# FORKGUARD_MAIN_BOARD.net
KiCad netlist of a schematic drawn in EasyEDA Pro
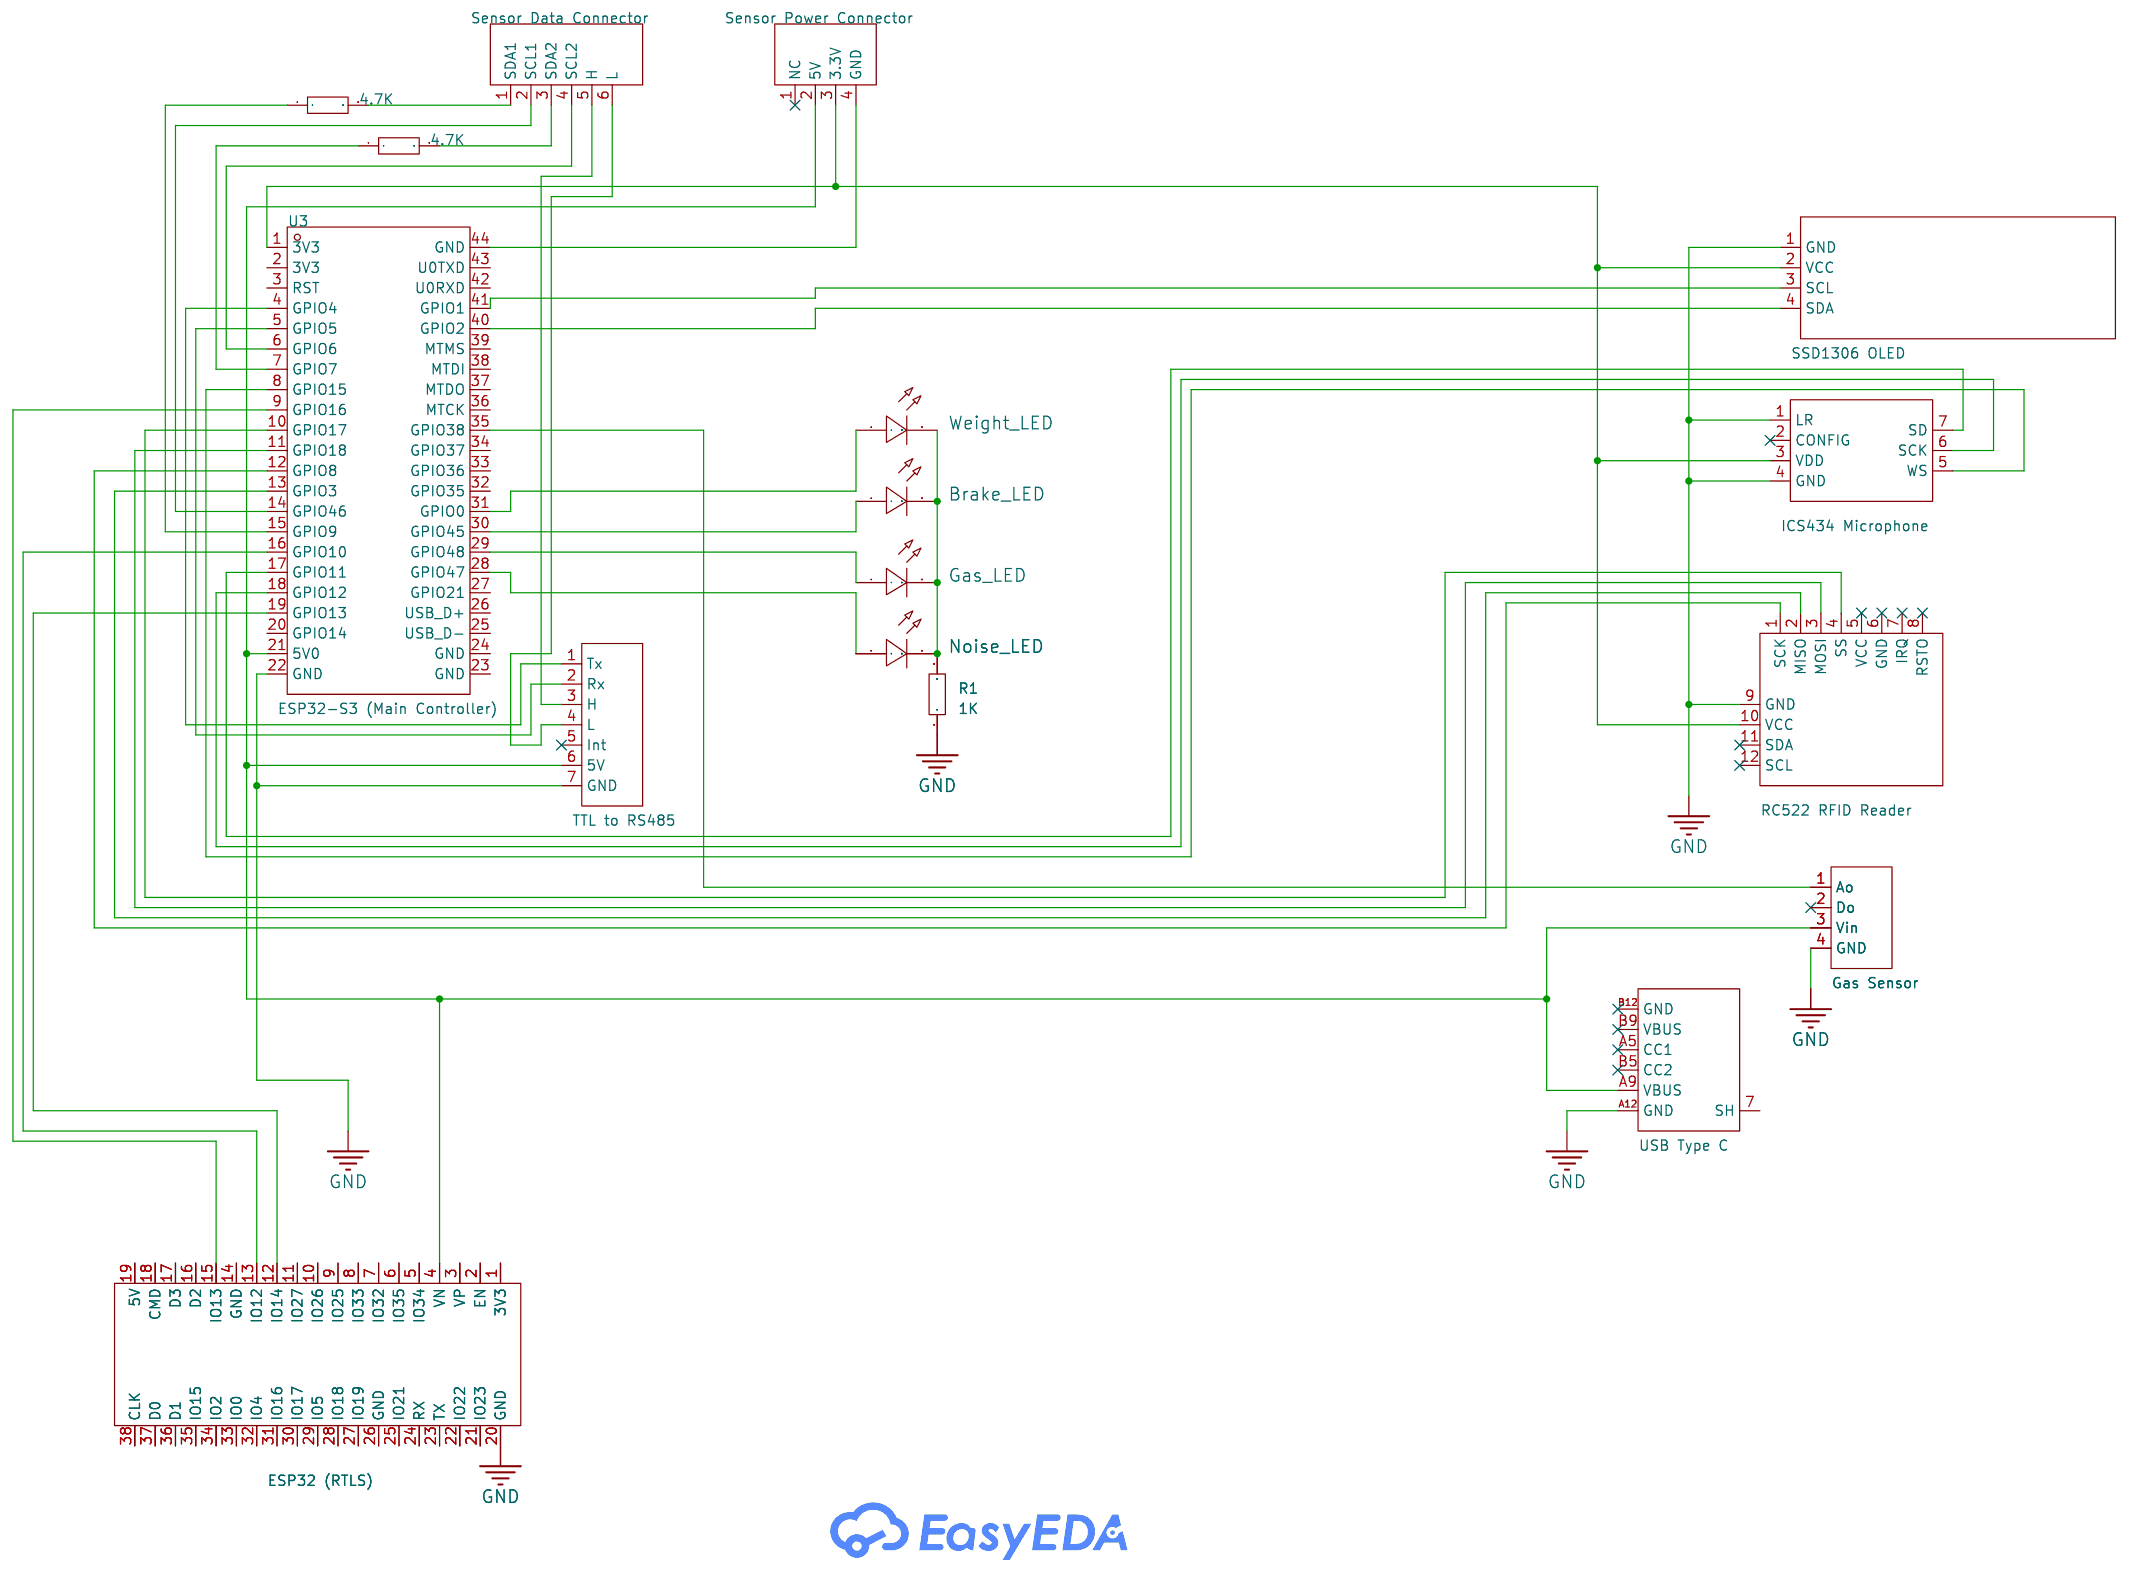
[diagram p0: schematic sheet]

(export (version "E")
  (design (tool "Eeschema 10.0.6"))
  (components
    (comp (ref "Brake_LED")
      (value "~")
      (footprint "easyedapro:LED0402-RD_YELLOW")
      (libsource (lib "easyedapro") (part "LED_R"))
    )
    (comp (ref "Display")
      (value "SSD1306 OLED")
      (footprint "easyedapro:OLED-TH_4P-L27.8-W27.3_MC096GW")
      (fields (field (name "Manufacturer Part") "MC096GW"))
      (libsource (lib "easyedapro") (part "MC096GW"))
    )
    (comp (ref "Gas_LED")
      (value "~")
      (footprint "easyedapro:LED0402-RD_YELLOW")
      (libsource (lib "easyedapro") (part "LED_R"))
    )
    (comp (ref "H1")
      (value "Sensor Data Connector")
      (footprint "easyedapro:HDR-TH_TW-06-01-T-S-150-085")
      (fields
        (field (name "Manufacturer Part") "TW-06-08-L-S-580-150")
        (field (name "Manufacturer") "SAMTEC")
      )
      (libsource (lib "easyedapro") (part "TW-06-08-L-S-580-150"))
    )
    (comp (ref "H2")
      (value "Sensor Power Connector")
      (footprint "easyedapro:HDR-TH_TW-04-06-T-S-433-120")
      (fields
        (field (name "Manufacturer Part") "TW-04-05-L-S-275-158")
        (field (name "Manufacturer") "SAMTEC")
      )
      (libsource (lib "easyedapro") (part "TW-04-05-L-S-275-158"))
    )
    (comp (ref "H5")
      (value "TTL to RS485")
      (footprint "easyedapro:HDR-TH_7P-P2.54_PBC07SAEN")
      (fields (field (name "Manufacturer Part") "PEC07SADN") (field (name "Manufacturer") "Sullins"))
      (libsource (lib "easyedapro") (part "PEC07SADN"))
    )
    (comp (ref "H6")
      (value "Gas Sensor")
      (footprint "easyedapro:HDR-TH_4P-P2.54-V-M_2")
      (fields (field (name "Manufacturer Part") "PEC04SFDN") (field (name "Manufacturer") "Sullins"))
      (libsource (lib "easyedapro") (part "PEC04SFDN"))
    )
    (comp (ref "Noise_LED")
      (value "~")
      (footprint "easyedapro:LED0402-RD_YELLOW")
      (libsource (lib "easyedapro") (part "LED_R"))
    )
    (comp (ref "R1") (value "10K") (footprint "easyedapro:R0603") (libsource (lib "easyedapro") (part "Res")))
    (comp (ref "R2") (value "10K") (footprint "easyedapro:R0603") (libsource (lib "easyedapro") (part "Res")))
    (comp (ref "R3")
      (value "10kΩ")
      (footprint "easyedapro:R0603")
      (libsource (lib "easyedapro") (part "Res"))
    )
    (comp (ref "U3")
      (value "ESP32-S3 (Main Controller)")
      (footprint "easyedapro:COMM-TH_L63.3-W25.4-P2.54-LS22.86")
      (fields (field (name "Manufacturer Part") "ESP32-S3-DEV-KIT-N8R8"))
      (libsource (lib "easyedapro") (part "ESP32-S3-DEV-KIT-N8R8"))
    )
    (comp (ref "U5")
      (value "ICS434 Microphone")
      (footprint "easyedapro:MIC-SMD_7P-L4.0-W3.0-P2.15-TL")
      (fields (field (name "Manufacturer Part") "DMM-4026-B-I2S-R") (field (name "Manufacturer") "PUIAUDIO"))
      (libsource (lib "easyedapro") (part "DMM-4026-B-I2S-R_C3171792"))
    )
    (comp (ref "U6")
      (value "RC522 RFID Reader")
      (footprint "easyedapro:COMM-TH_L42.7-W40.4_PN532_NFC_RFID")
      (fields (field (name "Manufacturer Part") "PN532 NFC RFID Module v4"))
      (libsource (lib "easyedapro") (part "PN532 NFC RFID MODULE V4"))
    )
    (comp (ref "U7")
      (value "ESP32 (RTLS)")
      (footprint "easyedapro:BULETM-SMD_ESP32-DEVKITC")
      (fields
        (field (name "Manufacturer Part") "ESP32-DEVKITC-VE")
        (field (name "Manufacturer") "ESPRESSIF(乐鑫)")
      )
      (libsource (lib "easyedapro") (part "ESP32-DEVKITC-VE"))
    )
    (comp (ref "USB1")
      (value "USB Type C")
      (footprint "easyedapro:USB-SMD_TYPE-C6P-ST")
      (fields (field (name "Manufacturer Part") "TCR51-65120601"))
      (libsource (lib "easyedapro") (part "TCR51-65120601"))
    )
    (comp (ref "Weight_LED")
      (value "~")
      (footprint "easyedapro:LED0402-RD_YELLOW")
      (libsource (lib "easyedapro") (part "LED_R"))
    )
  )
  (nets
    (net (code "1") (name "GND") (class "Default")
      (node (ref "Display") (pin "1") (pinfunction "GND_1") (pintype "unspecified"))
      (node (ref "H5") (pin "7") (pinfunction "GND_7") (pintype "unspecified"))
      (node (ref "H6") (pin "4") (pinfunction "GND_4") (pintype "unspecified"))
      (node (ref "R1") (pin "1") (pinfunction "1_1") (pintype "input"))
      (node (ref "U3") (pin "22") (pinfunction "GND_22") (pintype "unspecified"))
      (node (ref "U5") (pin "1") (pinfunction "LR_1") (pintype "unspecified"))
      (node (ref "U5") (pin "4") (pinfunction "GND_4") (pintype "unspecified"))
      (node (ref "U6") (pin "9") (pinfunction "GND_9") (pintype "unspecified"))
      (node (ref "U7") (pin "20") (pinfunction "GND_20") (pintype "unspecified"))
      (node (ref "USB1") (pin "A12") (pinfunction "GND_A12") (pintype "unspecified"))
    )
    (net (code "2") (name "Net-(Brake_LED-A)") (class "Default")
      (node (ref "Brake_LED") (pin "1") (pinfunction "A_1") (pintype "input"))
      (node (ref "U3") (pin "30") (pinfunction "GPIO45_30") (pintype "unspecified"))
    )
    (net (code "3") (name "Net-(Brake_LED-C)") (class "Default")
      (node (ref "Brake_LED") (pin "2") (pinfunction "C_2") (pintype "input"))
      (node (ref "Gas_LED") (pin "2") (pinfunction "C_2") (pintype "input"))
      (node (ref "Noise_LED") (pin "2") (pinfunction "C_2") (pintype "input"))
      (node (ref "R1") (pin "2") (pinfunction "2_2") (pintype "input"))
      (node (ref "Weight_LED") (pin "2") (pinfunction "C_2") (pintype "input"))
    )
    (net (code "4") (name "Net-(Display-SCL)") (class "Default")
      (node (ref "Display") (pin "3") (pinfunction "SCL_3") (pintype "unspecified"))
      (node (ref "U3") (pin "41") (pinfunction "GPIO1_41") (pintype "unspecified"))
    )
    (net (code "5") (name "Net-(Display-SDA)") (class "Default")
      (node (ref "Display") (pin "4") (pinfunction "SDA_4") (pintype "unspecified"))
      (node (ref "U3") (pin "40") (pinfunction "GPIO2_40") (pintype "unspecified"))
    )
    (net (code "6") (name "Net-(Display-VCC)") (class "Default")
      (node (ref "Display") (pin "2") (pinfunction "VCC_2") (pintype "unspecified"))
      (node (ref "H2") (pin "3") (pinfunction "3.3V_3") (pintype "unspecified"))
      (node (ref "U3") (pin "1") (pinfunction "3V3_1") (pintype "unspecified"))
      (node (ref "U5") (pin "3") (pinfunction "VDD_3") (pintype "unspecified"))
      (node (ref "U6") (pin "10") (pinfunction "VCC_10") (pintype "unspecified"))
    )
    (net (code "7") (name "Net-(Gas_LED-A)") (class "Default")
      (node (ref "Gas_LED") (pin "1") (pinfunction "A_1") (pintype "input"))
      (node (ref "U3") (pin "29") (pinfunction "GPIO48_29") (pintype "unspecified"))
    )
    (net (code "8") (name "Net-(H1-H)") (class "Default")
      (node (ref "H1") (pin "5") (pinfunction "H_5") (pintype "unspecified"))
      (node (ref "H5") (pin "3") (pinfunction "H_3") (pintype "unspecified"))
    )
    (net (code "9") (name "Net-(H1-L)") (class "Default")
      (node (ref "H1") (pin "6") (pinfunction "L_6") (pintype "unspecified"))
      (node (ref "H5") (pin "4") (pinfunction "L_4") (pintype "unspecified"))
    )
    (net (code "10") (name "Net-(H1-SCL1)") (class "Default")
      (node (ref "H1") (pin "2") (pinfunction "SCL1_2") (pintype "unspecified"))
      (node (ref "U3") (pin "14") (pinfunction "GPIO46_14") (pintype "unspecified"))
    )
    (net (code "11") (name "Net-(H1-SCL2)") (class "Default")
      (node (ref "H1") (pin "4") (pinfunction "SCL2_4") (pintype "unspecified"))
      (node (ref "U3") (pin "6") (pinfunction "GPIO6_6") (pintype "unspecified"))
    )
    (net (code "12") (name "Net-(H1-SDA1)") (class "Default")
      (node (ref "H1") (pin "1") (pinfunction "SDA1_1") (pintype "unspecified"))
      (node (ref "R2") (pin "2") (pinfunction "2_2") (pintype "input"))
    )
    (net (code "13") (name "Net-(H1-SDA2)") (class "Default")
      (node (ref "H1") (pin "3") (pinfunction "SDA2_3") (pintype "unspecified"))
      (node (ref "R3") (pin "2") (pinfunction "2_2") (pintype "input"))
    )
    (net (code "14") (name "Net-(H2-5V)") (class "Default")
      (node (ref "H2") (pin "2") (pinfunction "5V_2") (pintype "unspecified"))
      (node (ref "H5") (pin "6") (pinfunction "5V_6") (pintype "unspecified"))
      (node (ref "H6") (pin "3") (pinfunction "Vin_3") (pintype "unspecified"))
      (node (ref "U3") (pin "21") (pinfunction "5V0_21") (pintype "unspecified"))
      (node (ref "U7") (pin "4") (pinfunction "VN_4") (pintype "unspecified"))
      (node (ref "USB1") (pin "A9") (pinfunction "VBUS_A9") (pintype "unspecified"))
    )
    (net (code "15") (name "Net-(H2-GND)") (class "Default")
      (node (ref "H2") (pin "4") (pinfunction "GND_4") (pintype "unspecified"))
      (node (ref "U3") (pin "44") (pinfunction "GND_44") (pintype "unspecified"))
    )
    (net (code "16") (name "Net-(H5-Rx)") (class "Default")
      (node (ref "H5") (pin "2") (pinfunction "Rx_2") (pintype "unspecified"))
      (node (ref "U3") (pin "5") (pinfunction "GPIO5_5") (pintype "unspecified"))
    )
    (net (code "17") (name "Net-(H5-Tx)") (class "Default")
      (node (ref "H5") (pin "1") (pinfunction "Tx_1") (pintype "unspecified"))
      (node (ref "U3") (pin "4") (pinfunction "GPIO4_4") (pintype "unspecified"))
    )
    (net (code "18") (name "Net-(H6-Ao)") (class "Default")
      (node (ref "H6") (pin "1") (pinfunction "Ao_1") (pintype "unspecified"))
      (node (ref "U3") (pin "35") (pinfunction "GPIO38_35") (pintype "unspecified"))
    )
    (net (code "19") (name "Net-(Noise_LED-A)") (class "Default")
      (node (ref "Noise_LED") (pin "1") (pinfunction "A_1") (pintype "input"))
      (node (ref "U3") (pin "28") (pinfunction "GPIO47_28") (pintype "unspecified"))
    )
    (net (code "20") (name "Net-(U3-GPIO0)") (class "Default")
      (node (ref "U3") (pin "31") (pinfunction "GPIO0_31") (pintype "unspecified"))
      (node (ref "Weight_LED") (pin "1") (pinfunction "A_1") (pintype "input"))
    )
    (net (code "21") (name "Net-(U3-GPIO3)") (class "Default")
      (node (ref "U3") (pin "13") (pinfunction "GPIO3_13") (pintype "unspecified"))
      (node (ref "U6") (pin "2") (pinfunction "MISO_2") (pintype "unspecified"))
    )
    (net (code "22") (name "Net-(U3-GPIO7)") (class "Default")
      (node (ref "R3") (pin "1") (pinfunction "1_1") (pintype "input"))
      (node (ref "U3") (pin "7") (pinfunction "GPIO7_7") (pintype "unspecified"))
    )
    (net (code "23") (name "Net-(U3-GPIO8)") (class "Default")
      (node (ref "U3") (pin "12") (pinfunction "GPIO8_12") (pintype "unspecified"))
      (node (ref "U6") (pin "1") (pinfunction "SCK_1") (pintype "unspecified"))
    )
    (net (code "24") (name "Net-(U3-GPIO9)") (class "Default")
      (node (ref "R2") (pin "1") (pinfunction "1_1") (pintype "input"))
      (node (ref "U3") (pin "15") (pinfunction "GPIO9_15") (pintype "unspecified"))
    )
    (net (code "25") (name "Net-(U3-GPIO10)") (class "Default")
      (node (ref "U3") (pin "16") (pinfunction "GPIO10_16") (pintype "unspecified"))
      (node (ref "U7") (pin "13") (pinfunction "IO12_13") (pintype "unspecified"))
    )
    (net (code "26") (name "Net-(U3-GPIO11)") (class "Default")
      (node (ref "U3") (pin "17") (pinfunction "GPIO11_17") (pintype "unspecified"))
      (node (ref "U5") (pin "7") (pinfunction "SD_7") (pintype "unspecified"))
    )
    (net (code "27") (name "Net-(U3-GPIO12)") (class "Default")
      (node (ref "U3") (pin "18") (pinfunction "GPIO12_18") (pintype "unspecified"))
      (node (ref "U5") (pin "6") (pinfunction "SCK_6") (pintype "unspecified"))
    )
    (net (code "28") (name "Net-(U3-GPIO13)") (class "Default")
      (node (ref "U3") (pin "19") (pinfunction "GPIO13_19") (pintype "unspecified"))
      (node (ref "U7") (pin "12") (pinfunction "IO14_12") (pintype "unspecified"))
    )
    (net (code "29") (name "Net-(U3-GPIO15)") (class "Default")
      (node (ref "U3") (pin "8") (pinfunction "GPIO15_8") (pintype "unspecified"))
      (node (ref "U5") (pin "5") (pinfunction "WS_5") (pintype "unspecified"))
    )
    (net (code "30") (name "Net-(U3-GPIO16)") (class "Default")
      (node (ref "U3") (pin "9") (pinfunction "GPIO16_9") (pintype "unspecified"))
      (node (ref "U7") (pin "15") (pinfunction "IO13_15") (pintype "unspecified"))
    )
    (net (code "31") (name "Net-(U3-GPIO17)") (class "Default")
      (node (ref "U3") (pin "10") (pinfunction "GPIO17_10") (pintype "unspecified"))
      (node (ref "U6") (pin "4") (pinfunction "SS_4") (pintype "unspecified"))
    )
    (net (code "32") (name "Net-(U3-GPIO18)") (class "Default")
      (node (ref "U3") (pin "11") (pinfunction "GPIO18_11") (pintype "unspecified"))
      (node (ref "U6") (pin "3") (pinfunction "MOSI_3") (pintype "unspecified"))
    )
    (net (code "33") (name "unconnected-(H2-NC-Pad1)") (class "Default")
      (node (ref "H2") (pin "1") (pinfunction "NC_1") (pintype "unspecified+no_connect"))
    )
    (net (code "34") (name "unconnected-(H5-Int-Pad5)") (class "Default")
      (node (ref "H5") (pin "5") (pinfunction "Int_5") (pintype "unspecified+no_connect"))
    )
    (net (code "35") (name "unconnected-(H6-Do-Pad2)") (class "Default")
      (node (ref "H6") (pin "2") (pinfunction "Do_2") (pintype "unspecified+no_connect"))
    )
    (net (code "36") (name "unconnected-(U3-3V3-Pad2)") (class "Default")
      (node (ref "U3") (pin "2") (pinfunction "3V3_2") (pintype "unspecified"))
    )
    (net (code "37") (name "unconnected-(U3-GND-Pad23)") (class "Default")
      (node (ref "U3") (pin "23") (pinfunction "GND_23") (pintype "unspecified"))
    )
    (net (code "38") (name "unconnected-(U3-GND-Pad24)") (class "Default")
      (node (ref "U3") (pin "24") (pinfunction "GND_24") (pintype "unspecified"))
    )
    (net (code "39") (name "unconnected-(U3-GPIO14-Pad20)") (class "Default")
      (node (ref "U3") (pin "20") (pinfunction "GPIO14_20") (pintype "unspecified"))
    )
    (net (code "40") (name "unconnected-(U3-GPIO21-Pad27)") (class "Default")
      (node (ref "U3") (pin "27") (pinfunction "GPIO21_27") (pintype "unspecified"))
    )
    (net (code "41") (name "unconnected-(U3-GPIO35-Pad32)") (class "Default")
      (node (ref "U3") (pin "32") (pinfunction "GPIO35_32") (pintype "unspecified"))
    )
    (net (code "42") (name "unconnected-(U3-GPIO36-Pad33)") (class "Default")
      (node (ref "U3") (pin "33") (pinfunction "GPIO36_33") (pintype "unspecified"))
    )
    (net (code "43") (name "unconnected-(U3-GPIO37-Pad34)") (class "Default")
      (node (ref "U3") (pin "34") (pinfunction "GPIO37_34") (pintype "unspecified"))
    )
    (net (code "44") (name "unconnected-(U3-MTCK-Pad36)") (class "Default")
      (node (ref "U3") (pin "36") (pinfunction "MTCK_36") (pintype "unspecified"))
    )
    (net (code "45") (name "unconnected-(U3-MTDI-Pad38)") (class "Default")
      (node (ref "U3") (pin "38") (pinfunction "MTDI_38") (pintype "unspecified"))
    )
    (net (code "46") (name "unconnected-(U3-MTDO-Pad37)") (class "Default")
      (node (ref "U3") (pin "37") (pinfunction "MTDO_37") (pintype "unspecified"))
    )
    (net (code "47") (name "unconnected-(U3-MTMS-Pad39)") (class "Default")
      (node (ref "U3") (pin "39") (pinfunction "MTMS_39") (pintype "unspecified"))
    )
    (net (code "48") (name "unconnected-(U3-RST-Pad3)") (class "Default")
      (node (ref "U3") (pin "3") (pinfunction "RST_3") (pintype "unspecified"))
    )
    (net (code "49") (name "unconnected-(U3-U0RXD-Pad42)") (class "Default")
      (node (ref "U3") (pin "42") (pinfunction "U0RXD_42") (pintype "unspecified"))
    )
    (net (code "50") (name "unconnected-(U3-U0TXD-Pad43)") (class "Default")
      (node (ref "U3") (pin "43") (pinfunction "U0TXD_43") (pintype "unspecified"))
    )
    (net (code "51") (name "unconnected-(U3-USB_D+-Pad26)") (class "Default")
      (node (ref "U3") (pin "26") (pinfunction "USB_D+_26") (pintype "unspecified"))
    )
    (net (code "52") (name "unconnected-(U3-USB_D--Pad25)") (class "Default")
      (node (ref "U3") (pin "25") (pinfunction "USB_D-_25") (pintype "unspecified"))
    )
    (net (code "53") (name "unconnected-(U5-CONFIG-Pad2)") (class "Default")
      (node (ref "U5") (pin "2") (pinfunction "CONFIG_2") (pintype "unspecified+no_connect"))
    )
    (net (code "54") (name "unconnected-(U6-GND-Pad6)") (class "Default")
      (node (ref "U6") (pin "6") (pinfunction "GND_6") (pintype "unspecified+no_connect"))
    )
    (net (code "55") (name "unconnected-(U6-IRQ-Pad7)") (class "Default")
      (node (ref "U6") (pin "7") (pinfunction "IRQ_7") (pintype "unspecified+no_connect"))
    )
    (net (code "56") (name "unconnected-(U6-RSTO-Pad8)") (class "Default")
      (node (ref "U6") (pin "8") (pinfunction "RSTO_8") (pintype "unspecified+no_connect"))
    )
    (net (code "57") (name "unconnected-(U6-SCL-Pad12)") (class "Default")
      (node (ref "U6") (pin "12") (pinfunction "SCL_12") (pintype "unspecified+no_connect"))
    )
    (net (code "58") (name "unconnected-(U6-SDA-Pad11)") (class "Default")
      (node (ref "U6") (pin "11") (pinfunction "SDA_11") (pintype "unspecified+no_connect"))
    )
    (net (code "59") (name "unconnected-(U6-VCC-Pad5)") (class "Default")
      (node (ref "U6") (pin "5") (pinfunction "VCC_5") (pintype "unspecified+no_connect"))
    )
    (net (code "60") (name "unconnected-(U7-3V3-Pad1)") (class "Default")
      (node (ref "U7") (pin "1") (pinfunction "3V3_1") (pintype "unspecified"))
    )
    (net (code "61") (name "unconnected-(U7-5V-Pad19)") (class "Default")
      (node (ref "U7") (pin "19") (pinfunction "5V_19") (pintype "unspecified"))
    )
    (net (code "62") (name "unconnected-(U7-CLK-Pad38)") (class "Default")
      (node (ref "U7") (pin "38") (pinfunction "CLK_38") (pintype "unspecified"))
    )
    (net (code "63") (name "unconnected-(U7-CMD-Pad18)") (class "Default")
      (node (ref "U7") (pin "18") (pinfunction "CMD_18") (pintype "unspecified"))
    )
    (net (code "64") (name "unconnected-(U7-D0-Pad37)") (class "Default")
      (node (ref "U7") (pin "37") (pinfunction "D0_37") (pintype "unspecified"))
    )
    (net (code "65") (name "unconnected-(U7-D1-Pad36)") (class "Default")
      (node (ref "U7") (pin "36") (pinfunction "D1_36") (pintype "unspecified"))
    )
    (net (code "66") (name "unconnected-(U7-D2-Pad16)") (class "Default")
      (node (ref "U7") (pin "16") (pinfunction "D2_16") (pintype "unspecified"))
    )
    (net (code "67") (name "unconnected-(U7-D3-Pad17)") (class "Default")
      (node (ref "U7") (pin "17") (pinfunction "D3_17") (pintype "unspecified"))
    )
    (net (code "68") (name "unconnected-(U7-EN-Pad2)") (class "Default")
      (node (ref "U7") (pin "2") (pinfunction "EN_2") (pintype "unspecified"))
    )
    (net (code "69") (name "unconnected-(U7-GND-Pad14)") (class "Default")
      (node (ref "U7") (pin "14") (pinfunction "GND_14") (pintype "unspecified"))
    )
    (net (code "70") (name "unconnected-(U7-GND-Pad26)") (class "Default")
      (node (ref "U7") (pin "26") (pinfunction "GND_26") (pintype "unspecified"))
    )
    (net (code "71") (name "unconnected-(U7-IO0-Pad33)") (class "Default")
      (node (ref "U7") (pin "33") (pinfunction "IO0_33") (pintype "unspecified"))
    )
    (net (code "72") (name "unconnected-(U7-IO2-Pad34)") (class "Default")
      (node (ref "U7") (pin "34") (pinfunction "IO2_34") (pintype "unspecified"))
    )
    (net (code "73") (name "unconnected-(U7-IO4-Pad32)") (class "Default")
      (node (ref "U7") (pin "32") (pinfunction "IO4_32") (pintype "unspecified"))
    )
    (net (code "74") (name "unconnected-(U7-IO5-Pad29)") (class "Default")
      (node (ref "U7") (pin "29") (pinfunction "IO5_29") (pintype "unspecified"))
    )
    (net (code "75") (name "unconnected-(U7-IO15-Pad35)") (class "Default")
      (node (ref "U7") (pin "35") (pinfunction "IO15_35") (pintype "unspecified"))
    )
    (net (code "76") (name "unconnected-(U7-IO16-Pad31)") (class "Default")
      (node (ref "U7") (pin "31") (pinfunction "IO16_31") (pintype "unspecified"))
    )
    (net (code "77") (name "unconnected-(U7-IO17-Pad30)") (class "Default")
      (node (ref "U7") (pin "30") (pinfunction "IO17_30") (pintype "unspecified"))
    )
    (net (code "78") (name "unconnected-(U7-IO18-Pad28)") (class "Default")
      (node (ref "U7") (pin "28") (pinfunction "IO18_28") (pintype "unspecified"))
    )
    (net (code "79") (name "unconnected-(U7-IO19-Pad27)") (class "Default")
      (node (ref "U7") (pin "27") (pinfunction "IO19_27") (pintype "unspecified"))
    )
    (net (code "80") (name "unconnected-(U7-IO21-Pad25)") (class "Default")
      (node (ref "U7") (pin "25") (pinfunction "IO21_25") (pintype "unspecified"))
    )
    (net (code "81") (name "unconnected-(U7-IO22-Pad22)") (class "Default")
      (node (ref "U7") (pin "22") (pinfunction "IO22_22") (pintype "unspecified"))
    )
    (net (code "82") (name "unconnected-(U7-IO23-Pad21)") (class "Default")
      (node (ref "U7") (pin "21") (pinfunction "IO23_21") (pintype "unspecified"))
    )
    (net (code "83") (name "unconnected-(U7-IO25-Pad9)") (class "Default")
      (node (ref "U7") (pin "9") (pinfunction "IO25_9") (pintype "unspecified"))
    )
    (net (code "84") (name "unconnected-(U7-IO26-Pad10)") (class "Default")
      (node (ref "U7") (pin "10") (pinfunction "IO26_10") (pintype "unspecified"))
    )
    (net (code "85") (name "unconnected-(U7-IO27-Pad11)") (class "Default")
      (node (ref "U7") (pin "11") (pinfunction "IO27_11") (pintype "unspecified"))
    )
    (net (code "86") (name "unconnected-(U7-IO32-Pad7)") (class "Default")
      (node (ref "U7") (pin "7") (pinfunction "IO32_7") (pintype "unspecified"))
    )
    (net (code "87") (name "unconnected-(U7-IO33-Pad8)") (class "Default")
      (node (ref "U7") (pin "8") (pinfunction "IO33_8") (pintype "unspecified"))
    )
    (net (code "88") (name "unconnected-(U7-IO34-Pad5)") (class "Default")
      (node (ref "U7") (pin "5") (pinfunction "IO34_5") (pintype "unspecified"))
    )
    (net (code "89") (name "unconnected-(U7-IO35-Pad6)") (class "Default")
      (node (ref "U7") (pin "6") (pinfunction "IO35_6") (pintype "unspecified"))
    )
    (net (code "90") (name "unconnected-(U7-RX-Pad24)") (class "Default")
      (node (ref "U7") (pin "24") (pinfunction "RX_24") (pintype "unspecified"))
    )
    (net (code "91") (name "unconnected-(U7-TX-Pad23)") (class "Default")
      (node (ref "U7") (pin "23") (pinfunction "TX_23") (pintype "unspecified"))
    )
    (net (code "92") (name "unconnected-(U7-VP-Pad3)") (class "Default")
      (node (ref "U7") (pin "3") (pinfunction "VP_3") (pintype "unspecified"))
    )
    (net (code "93") (name "unconnected-(USB1-CC1-PadA5)") (class "Default")
      (node (ref "USB1") (pin "A5") (pinfunction "CC1_A5") (pintype "unspecified+no_connect"))
    )
    (net (code "94") (name "unconnected-(USB1-CC2-PadB5)") (class "Default")
      (node (ref "USB1") (pin "B5") (pinfunction "CC2_B5") (pintype "unspecified+no_connect"))
    )
    (net (code "95") (name "unconnected-(USB1-GND-PadB12)") (class "Default")
      (node (ref "USB1") (pin "B12") (pinfunction "GND_B12") (pintype "unspecified+no_connect"))
    )
    (net (code "96") (name "unconnected-(USB1-SH-Pad7)") (class "Default")
      (node (ref "USB1") (pin "7") (pinfunction "SH_7") (pintype "unspecified"))
    )
    (net (code "97") (name "unconnected-(USB1-VBUS-PadB9)") (class "Default")
      (node (ref "USB1") (pin "B9") (pinfunction "VBUS_B9") (pintype "unspecified+no_connect"))
    )
  )
)
